# Output.net
KiCad netlist of a schematic drawn in EAGLE
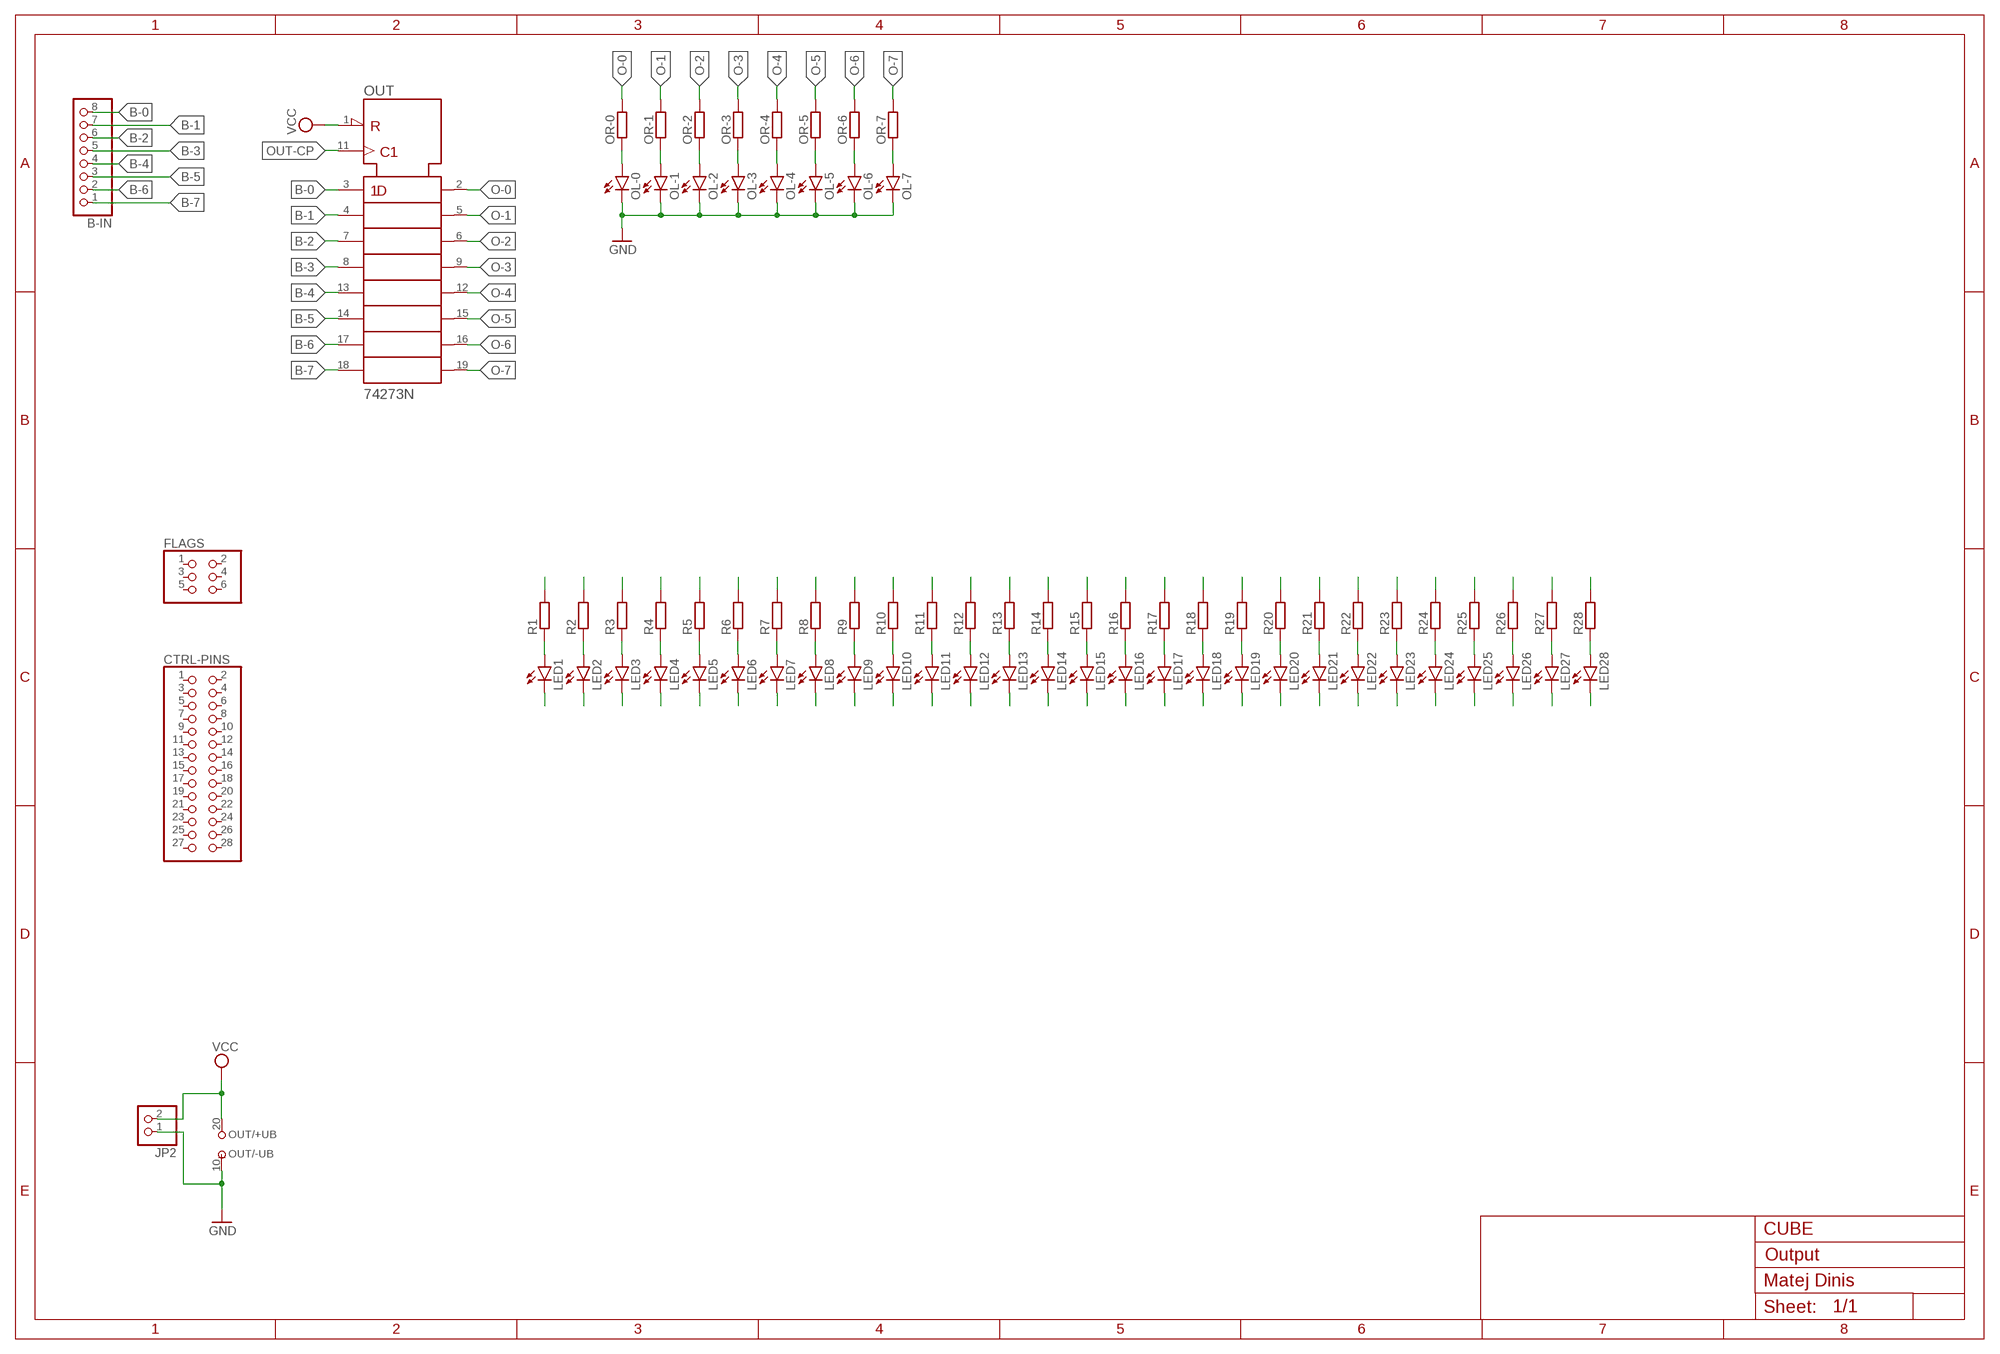
[diagram p0: schematic, sheet 1]

(export (version "E")
  (design (tool "Eeschema 10.0.6"))
  (components
    (comp (ref "B-IN")
      (value "PINHD-1X8")
      (footprint "eagle-import:1X08")
      (libsource (lib "eagle-import") (part "PINHD-1X8"))
    )
    (comp (ref "CTRL-PINS")
      (value "PINHD-2X14")
      (footprint "eagle-import:2X14")
      (libsource (lib "eagle-import") (part "PINHD-2X14"))
    )
    (comp (ref "FLAGS")
      (value "PINHD-2X3")
      (footprint "eagle-import:2X03")
      (libsource (lib "eagle-import") (part "PINHD-2X3"))
    )
    (comp (ref "JP2")
      (value "PINHD-1X2")
      (footprint "eagle-import:1X02")
      (libsource (lib "eagle-import") (part "PINHD-1X2"))
    )
    (comp (ref "LED1")
      (value "LED5MM")
      (footprint "eagle-import:LED5MM")
      (libsource (lib "eagle-import") (part "LED5MM"))
    )
    (comp (ref "LED2")
      (value "LED5MM")
      (footprint "eagle-import:LED5MM")
      (libsource (lib "eagle-import") (part "LED5MM"))
    )
    (comp (ref "LED3")
      (value "LED5MM")
      (footprint "eagle-import:LED5MM")
      (libsource (lib "eagle-import") (part "LED5MM"))
    )
    (comp (ref "LED4")
      (value "LED5MM")
      (footprint "eagle-import:LED5MM")
      (libsource (lib "eagle-import") (part "LED5MM"))
    )
    (comp (ref "LED5")
      (value "LED5MM")
      (footprint "eagle-import:LED5MM")
      (libsource (lib "eagle-import") (part "LED5MM"))
    )
    (comp (ref "LED6")
      (value "LED5MM")
      (footprint "eagle-import:LED5MM")
      (libsource (lib "eagle-import") (part "LED5MM"))
    )
    (comp (ref "LED7")
      (value "LED5MM")
      (footprint "eagle-import:LED5MM")
      (libsource (lib "eagle-import") (part "LED5MM"))
    )
    (comp (ref "LED8")
      (value "LED5MM")
      (footprint "eagle-import:LED5MM")
      (libsource (lib "eagle-import") (part "LED5MM"))
    )
    (comp (ref "LED9")
      (value "LED5MM")
      (footprint "eagle-import:LED5MM")
      (libsource (lib "eagle-import") (part "LED5MM"))
    )
    (comp (ref "LED10")
      (value "LED5MM")
      (footprint "eagle-import:LED5MM")
      (libsource (lib "eagle-import") (part "LED5MM"))
    )
    (comp (ref "LED11")
      (value "LED5MM")
      (footprint "eagle-import:LED5MM")
      (libsource (lib "eagle-import") (part "LED5MM"))
    )
    (comp (ref "LED12")
      (value "LED5MM")
      (footprint "eagle-import:LED5MM")
      (libsource (lib "eagle-import") (part "LED5MM"))
    )
    (comp (ref "LED13")
      (value "LED5MM")
      (footprint "eagle-import:LED5MM")
      (libsource (lib "eagle-import") (part "LED5MM"))
    )
    (comp (ref "LED14")
      (value "LED5MM")
      (footprint "eagle-import:LED5MM")
      (libsource (lib "eagle-import") (part "LED5MM"))
    )
    (comp (ref "LED15")
      (value "LED5MM")
      (footprint "eagle-import:LED5MM")
      (libsource (lib "eagle-import") (part "LED5MM"))
    )
    (comp (ref "LED16")
      (value "LED5MM")
      (footprint "eagle-import:LED5MM")
      (libsource (lib "eagle-import") (part "LED5MM"))
    )
    (comp (ref "LED17")
      (value "LED5MM")
      (footprint "eagle-import:LED5MM")
      (libsource (lib "eagle-import") (part "LED5MM"))
    )
    (comp (ref "LED18")
      (value "LED5MM")
      (footprint "eagle-import:LED5MM")
      (libsource (lib "eagle-import") (part "LED5MM"))
    )
    (comp (ref "LED19")
      (value "LED5MM")
      (footprint "eagle-import:LED5MM")
      (libsource (lib "eagle-import") (part "LED5MM"))
    )
    (comp (ref "LED20")
      (value "LED5MM")
      (footprint "eagle-import:LED5MM")
      (libsource (lib "eagle-import") (part "LED5MM"))
    )
    (comp (ref "LED21")
      (value "LED5MM")
      (footprint "eagle-import:LED5MM")
      (libsource (lib "eagle-import") (part "LED5MM"))
    )
    (comp (ref "LED22")
      (value "LED5MM")
      (footprint "eagle-import:LED5MM")
      (libsource (lib "eagle-import") (part "LED5MM"))
    )
    (comp (ref "LED23")
      (value "LED5MM")
      (footprint "eagle-import:LED5MM")
      (libsource (lib "eagle-import") (part "LED5MM"))
    )
    (comp (ref "LED24")
      (value "LED5MM")
      (footprint "eagle-import:LED5MM")
      (libsource (lib "eagle-import") (part "LED5MM"))
    )
    (comp (ref "LED25")
      (value "LED5MM")
      (footprint "eagle-import:LED5MM")
      (libsource (lib "eagle-import") (part "LED5MM"))
    )
    (comp (ref "LED26")
      (value "LED5MM")
      (footprint "eagle-import:LED5MM")
      (libsource (lib "eagle-import") (part "LED5MM"))
    )
    (comp (ref "LED27")
      (value "LED5MM")
      (footprint "eagle-import:LED5MM")
      (libsource (lib "eagle-import") (part "LED5MM"))
    )
    (comp (ref "LED28")
      (value "LED5MM")
      (footprint "eagle-import:LED5MM")
      (libsource (lib "eagle-import") (part "LED5MM"))
    )
    (comp (ref "OL-0")
      (value "LED5MM")
      (footprint "eagle-import:LED5MM")
      (libsource (lib "eagle-import") (part "LED5MM"))
    )
    (comp (ref "OL-1")
      (value "LED5MM")
      (footprint "eagle-import:LED5MM")
      (libsource (lib "eagle-import") (part "LED5MM"))
    )
    (comp (ref "OL-2")
      (value "LED5MM")
      (footprint "eagle-import:LED5MM")
      (libsource (lib "eagle-import") (part "LED5MM"))
    )
    (comp (ref "OL-3")
      (value "LED5MM")
      (footprint "eagle-import:LED5MM")
      (libsource (lib "eagle-import") (part "LED5MM"))
    )
    (comp (ref "OL-4")
      (value "LED5MM")
      (footprint "eagle-import:LED5MM")
      (libsource (lib "eagle-import") (part "LED5MM"))
    )
    (comp (ref "OL-5")
      (value "LED5MM")
      (footprint "eagle-import:LED5MM")
      (libsource (lib "eagle-import") (part "LED5MM"))
    )
    (comp (ref "OL-6")
      (value "LED5MM")
      (footprint "eagle-import:LED5MM")
      (libsource (lib "eagle-import") (part "LED5MM"))
    )
    (comp (ref "OL-7")
      (value "LED5MM")
      (footprint "eagle-import:LED5MM")
      (libsource (lib "eagle-import") (part "LED5MM"))
    )
    (comp (ref "OR-0")
      (value "R-EU_0207/10")
      (footprint "eagle-import:0207_10")
      (libsource (lib "eagle-import") (part "R-EU_0207/10"))
    )
    (comp (ref "OR-1")
      (value "R-EU_0207/10")
      (footprint "eagle-import:0207_10")
      (libsource (lib "eagle-import") (part "R-EU_0207/10"))
    )
    (comp (ref "OR-2")
      (value "R-EU_0207/10")
      (footprint "eagle-import:0207_10")
      (libsource (lib "eagle-import") (part "R-EU_0207/10"))
    )
    (comp (ref "OR-3")
      (value "R-EU_0207/10")
      (footprint "eagle-import:0207_10")
      (libsource (lib "eagle-import") (part "R-EU_0207/10"))
    )
    (comp (ref "OR-4")
      (value "R-EU_0207/10")
      (footprint "eagle-import:0207_10")
      (libsource (lib "eagle-import") (part "R-EU_0207/10"))
    )
    (comp (ref "OR-5")
      (value "R-EU_0207/10")
      (footprint "eagle-import:0207_10")
      (libsource (lib "eagle-import") (part "R-EU_0207/10"))
    )
    (comp (ref "OR-6")
      (value "R-EU_0207/10")
      (footprint "eagle-import:0207_10")
      (libsource (lib "eagle-import") (part "R-EU_0207/10"))
    )
    (comp (ref "OR-7")
      (value "R-EU_0207/10")
      (footprint "eagle-import:0207_10")
      (libsource (lib "eagle-import") (part "R-EU_0207/10"))
    )
    (comp (ref "OUT")
      (value "74273N")
      (footprint "eagle-import:DIL20")
      (libsource (lib "eagle-import") (part "74273N"))
    )
    (comp (ref "R1")
      (value "R-EU_0207/10")
      (footprint "eagle-import:0207_10")
      (libsource (lib "eagle-import") (part "R-EU_0207/10"))
    )
    (comp (ref "R2")
      (value "R-EU_0207/10")
      (footprint "eagle-import:0207_10")
      (libsource (lib "eagle-import") (part "R-EU_0207/10"))
    )
    (comp (ref "R3")
      (value "R-EU_0207/10")
      (footprint "eagle-import:0207_10")
      (libsource (lib "eagle-import") (part "R-EU_0207/10"))
    )
    (comp (ref "R4")
      (value "R-EU_0207/10")
      (footprint "eagle-import:0207_10")
      (libsource (lib "eagle-import") (part "R-EU_0207/10"))
    )
    (comp (ref "R5")
      (value "R-EU_0207/10")
      (footprint "eagle-import:0207_10")
      (libsource (lib "eagle-import") (part "R-EU_0207/10"))
    )
    (comp (ref "R6")
      (value "R-EU_0207/10")
      (footprint "eagle-import:0207_10")
      (libsource (lib "eagle-import") (part "R-EU_0207/10"))
    )
    (comp (ref "R7")
      (value "R-EU_0207/10")
      (footprint "eagle-import:0207_10")
      (libsource (lib "eagle-import") (part "R-EU_0207/10"))
    )
    (comp (ref "R8")
      (value "R-EU_0207/10")
      (footprint "eagle-import:0207_10")
      (libsource (lib "eagle-import") (part "R-EU_0207/10"))
    )
    (comp (ref "R9")
      (value "R-EU_0207/10")
      (footprint "eagle-import:0207_10")
      (libsource (lib "eagle-import") (part "R-EU_0207/10"))
    )
    (comp (ref "R10")
      (value "R-EU_0207/10")
      (footprint "eagle-import:0207_10")
      (libsource (lib "eagle-import") (part "R-EU_0207/10"))
    )
    (comp (ref "R11")
      (value "R-EU_0207/10")
      (footprint "eagle-import:0207_10")
      (libsource (lib "eagle-import") (part "R-EU_0207/10"))
    )
    (comp (ref "R12")
      (value "R-EU_0207/10")
      (footprint "eagle-import:0207_10")
      (libsource (lib "eagle-import") (part "R-EU_0207/10"))
    )
    (comp (ref "R13")
      (value "R-EU_0207/10")
      (footprint "eagle-import:0207_10")
      (libsource (lib "eagle-import") (part "R-EU_0207/10"))
    )
    (comp (ref "R14")
      (value "R-EU_0207/10")
      (footprint "eagle-import:0207_10")
      (libsource (lib "eagle-import") (part "R-EU_0207/10"))
    )
    (comp (ref "R15")
      (value "R-EU_0207/10")
      (footprint "eagle-import:0207_10")
      (libsource (lib "eagle-import") (part "R-EU_0207/10"))
    )
    (comp (ref "R16")
      (value "R-EU_0207/10")
      (footprint "eagle-import:0207_10")
      (libsource (lib "eagle-import") (part "R-EU_0207/10"))
    )
    (comp (ref "R17")
      (value "R-EU_0207/10")
      (footprint "eagle-import:0207_10")
      (libsource (lib "eagle-import") (part "R-EU_0207/10"))
    )
    (comp (ref "R18")
      (value "R-EU_0207/10")
      (footprint "eagle-import:0207_10")
      (libsource (lib "eagle-import") (part "R-EU_0207/10"))
    )
    (comp (ref "R19")
      (value "R-EU_0207/10")
      (footprint "eagle-import:0207_10")
      (libsource (lib "eagle-import") (part "R-EU_0207/10"))
    )
    (comp (ref "R20")
      (value "R-EU_0207/10")
      (footprint "eagle-import:0207_10")
      (libsource (lib "eagle-import") (part "R-EU_0207/10"))
    )
    (comp (ref "R21")
      (value "R-EU_0207/10")
      (footprint "eagle-import:0207_10")
      (libsource (lib "eagle-import") (part "R-EU_0207/10"))
    )
    (comp (ref "R22")
      (value "R-EU_0207/10")
      (footprint "eagle-import:0207_10")
      (libsource (lib "eagle-import") (part "R-EU_0207/10"))
    )
    (comp (ref "R23")
      (value "R-EU_0207/10")
      (footprint "eagle-import:0207_10")
      (libsource (lib "eagle-import") (part "R-EU_0207/10"))
    )
    (comp (ref "R24")
      (value "R-EU_0207/10")
      (footprint "eagle-import:0207_10")
      (libsource (lib "eagle-import") (part "R-EU_0207/10"))
    )
    (comp (ref "R25")
      (value "R-EU_0207/10")
      (footprint "eagle-import:0207_10")
      (libsource (lib "eagle-import") (part "R-EU_0207/10"))
    )
    (comp (ref "R26")
      (value "R-EU_0207/10")
      (footprint "eagle-import:0207_10")
      (libsource (lib "eagle-import") (part "R-EU_0207/10"))
    )
    (comp (ref "R27")
      (value "R-EU_0207/10")
      (footprint "eagle-import:0207_10")
      (libsource (lib "eagle-import") (part "R-EU_0207/10"))
    )
    (comp (ref "R28")
      (value "R-EU_0207/10")
      (footprint "eagle-import:0207_10")
      (libsource (lib "eagle-import") (part "R-EU_0207/10"))
    )
  )
  (nets
    (net (code "1") (name "B-0") (class "Default")
      (node (ref "B-IN") (pin "8") (pinfunction "8_8") (pintype "passive"))
      (node (ref "OUT") (pin "3") (pinfunction "1D_3") (pintype "input"))
    )
    (net (code "2") (name "B-1") (class "Default")
      (node (ref "B-IN") (pin "7") (pinfunction "7_7") (pintype "passive"))
      (node (ref "OUT") (pin "4") (pinfunction "2D_4") (pintype "input"))
    )
    (net (code "3") (name "B-2") (class "Default")
      (node (ref "B-IN") (pin "6") (pinfunction "6_6") (pintype "passive"))
      (node (ref "OUT") (pin "7") (pinfunction "3D_7") (pintype "input"))
    )
    (net (code "4") (name "B-3") (class "Default")
      (node (ref "B-IN") (pin "5") (pinfunction "5_5") (pintype "passive"))
      (node (ref "OUT") (pin "8") (pinfunction "4D_8") (pintype "input"))
    )
    (net (code "5") (name "B-4") (class "Default")
      (node (ref "B-IN") (pin "4") (pinfunction "4_4") (pintype "passive"))
      (node (ref "OUT") (pin "13") (pinfunction "5D_13") (pintype "input"))
    )
    (net (code "6") (name "B-5") (class "Default")
      (node (ref "B-IN") (pin "3") (pinfunction "3_3") (pintype "passive"))
      (node (ref "OUT") (pin "14") (pinfunction "6D_14") (pintype "input"))
    )
    (net (code "7") (name "B-6") (class "Default")
      (node (ref "B-IN") (pin "2") (pinfunction "2_2") (pintype "passive"))
      (node (ref "OUT") (pin "17") (pinfunction "7D_17") (pintype "input"))
    )
    (net (code "8") (name "B-7") (class "Default")
      (node (ref "B-IN") (pin "1") (pinfunction "1_1") (pintype "passive"))
      (node (ref "OUT") (pin "18") (pinfunction "8D_18") (pintype "input"))
    )
    (net (code "9") (name "GND") (class "Default")
      (node (ref "JP2") (pin "1") (pinfunction "1_1") (pintype "passive"))
      (node (ref "OL-0") (pin "K") (pinfunction "C_K") (pintype "passive"))
      (node (ref "OL-1") (pin "K") (pinfunction "C_K") (pintype "passive"))
      (node (ref "OL-2") (pin "K") (pinfunction "C_K") (pintype "passive"))
      (node (ref "OL-3") (pin "K") (pinfunction "C_K") (pintype "passive"))
      (node (ref "OL-4") (pin "K") (pinfunction "C_K") (pintype "passive"))
      (node (ref "OL-5") (pin "K") (pinfunction "C_K") (pintype "passive"))
      (node (ref "OL-6") (pin "K") (pinfunction "C_K") (pintype "passive"))
      (node (ref "OL-7") (pin "K") (pinfunction "C_K") (pintype "passive"))
      (node (ref "OUT") (pin "10") (pinfunction "-UB_10") (pintype "power_in"))
    )
    (net (code "10") (name "Net-(LED1-PadA)") (class "Default")
      (node (ref "LED1") (pin "A") (pinfunction "A_A") (pintype "passive"))
      (node (ref "R1") (pin "1") (pinfunction "1_1") (pintype "passive"))
    )
    (net (code "11") (name "Net-(LED2-PadA)") (class "Default")
      (node (ref "LED2") (pin "A") (pinfunction "A_A") (pintype "passive"))
      (node (ref "R2") (pin "1") (pinfunction "1_1") (pintype "passive"))
    )
    (net (code "12") (name "Net-(LED3-PadA)") (class "Default")
      (node (ref "LED3") (pin "A") (pinfunction "A_A") (pintype "passive"))
      (node (ref "R3") (pin "1") (pinfunction "1_1") (pintype "passive"))
    )
    (net (code "13") (name "Net-(LED4-PadA)") (class "Default")
      (node (ref "LED4") (pin "A") (pinfunction "A_A") (pintype "passive"))
      (node (ref "R4") (pin "1") (pinfunction "1_1") (pintype "passive"))
    )
    (net (code "14") (name "Net-(LED5-PadA)") (class "Default")
      (node (ref "LED5") (pin "A") (pinfunction "A_A") (pintype "passive"))
      (node (ref "R5") (pin "1") (pinfunction "1_1") (pintype "passive"))
    )
    (net (code "15") (name "Net-(LED6-PadA)") (class "Default")
      (node (ref "LED6") (pin "A") (pinfunction "A_A") (pintype "passive"))
      (node (ref "R6") (pin "1") (pinfunction "1_1") (pintype "passive"))
    )
    (net (code "16") (name "Net-(LED7-PadA)") (class "Default")
      (node (ref "LED7") (pin "A") (pinfunction "A_A") (pintype "passive"))
      (node (ref "R7") (pin "1") (pinfunction "1_1") (pintype "passive"))
    )
    (net (code "17") (name "Net-(LED8-PadA)") (class "Default")
      (node (ref "LED8") (pin "A") (pinfunction "A_A") (pintype "passive"))
      (node (ref "R8") (pin "1") (pinfunction "1_1") (pintype "passive"))
    )
    (net (code "18") (name "Net-(LED9-PadA)") (class "Default")
      (node (ref "LED9") (pin "A") (pinfunction "A_A") (pintype "passive"))
      (node (ref "R9") (pin "1") (pinfunction "1_1") (pintype "passive"))
    )
    (net (code "19") (name "Net-(LED10-PadA)") (class "Default")
      (node (ref "LED10") (pin "A") (pinfunction "A_A") (pintype "passive"))
      (node (ref "R10") (pin "1") (pinfunction "1_1") (pintype "passive"))
    )
    (net (code "20") (name "Net-(LED11-PadA)") (class "Default")
      (node (ref "LED11") (pin "A") (pinfunction "A_A") (pintype "passive"))
      (node (ref "R11") (pin "1") (pinfunction "1_1") (pintype "passive"))
    )
    (net (code "21") (name "Net-(LED12-PadA)") (class "Default")
      (node (ref "LED12") (pin "A") (pinfunction "A_A") (pintype "passive"))
      (node (ref "R12") (pin "1") (pinfunction "1_1") (pintype "passive"))
    )
    (net (code "22") (name "Net-(LED13-PadA)") (class "Default")
      (node (ref "LED13") (pin "A") (pinfunction "A_A") (pintype "passive"))
      (node (ref "R13") (pin "1") (pinfunction "1_1") (pintype "passive"))
    )
    (net (code "23") (name "Net-(LED14-PadA)") (class "Default")
      (node (ref "LED14") (pin "A") (pinfunction "A_A") (pintype "passive"))
      (node (ref "R14") (pin "1") (pinfunction "1_1") (pintype "passive"))
    )
    (net (code "24") (name "Net-(LED15-PadA)") (class "Default")
      (node (ref "LED15") (pin "A") (pinfunction "A_A") (pintype "passive"))
      (node (ref "R15") (pin "1") (pinfunction "1_1") (pintype "passive"))
    )
    (net (code "25") (name "Net-(LED16-PadA)") (class "Default")
      (node (ref "LED16") (pin "A") (pinfunction "A_A") (pintype "passive"))
      (node (ref "R16") (pin "1") (pinfunction "1_1") (pintype "passive"))
    )
    (net (code "26") (name "Net-(LED17-PadA)") (class "Default")
      (node (ref "LED17") (pin "A") (pinfunction "A_A") (pintype "passive"))
      (node (ref "R17") (pin "1") (pinfunction "1_1") (pintype "passive"))
    )
    (net (code "27") (name "Net-(LED18-PadA)") (class "Default")
      (node (ref "LED18") (pin "A") (pinfunction "A_A") (pintype "passive"))
      (node (ref "R18") (pin "1") (pinfunction "1_1") (pintype "passive"))
    )
    (net (code "28") (name "Net-(LED19-PadA)") (class "Default")
      (node (ref "LED19") (pin "A") (pinfunction "A_A") (pintype "passive"))
      (node (ref "R19") (pin "1") (pinfunction "1_1") (pintype "passive"))
    )
    (net (code "29") (name "Net-(LED20-PadA)") (class "Default")
      (node (ref "LED20") (pin "A") (pinfunction "A_A") (pintype "passive"))
      (node (ref "R20") (pin "1") (pinfunction "1_1") (pintype "passive"))
    )
    (net (code "30") (name "Net-(LED21-PadA)") (class "Default")
      (node (ref "LED21") (pin "A") (pinfunction "A_A") (pintype "passive"))
      (node (ref "R21") (pin "1") (pinfunction "1_1") (pintype "passive"))
    )
    (net (code "31") (name "Net-(LED22-PadA)") (class "Default")
      (node (ref "LED22") (pin "A") (pinfunction "A_A") (pintype "passive"))
      (node (ref "R22") (pin "1") (pinfunction "1_1") (pintype "passive"))
    )
    (net (code "32") (name "Net-(LED23-PadA)") (class "Default")
      (node (ref "LED23") (pin "A") (pinfunction "A_A") (pintype "passive"))
      (node (ref "R23") (pin "1") (pinfunction "1_1") (pintype "passive"))
    )
    (net (code "33") (name "Net-(LED24-PadA)") (class "Default")
      (node (ref "LED24") (pin "A") (pinfunction "A_A") (pintype "passive"))
      (node (ref "R24") (pin "1") (pinfunction "1_1") (pintype "passive"))
    )
    (net (code "34") (name "Net-(LED25-PadA)") (class "Default")
      (node (ref "LED25") (pin "A") (pinfunction "A_A") (pintype "passive"))
      (node (ref "R25") (pin "1") (pinfunction "1_1") (pintype "passive"))
    )
    (net (code "35") (name "Net-(LED26-PadA)") (class "Default")
      (node (ref "LED26") (pin "A") (pinfunction "A_A") (pintype "passive"))
      (node (ref "R26") (pin "1") (pinfunction "1_1") (pintype "passive"))
    )
    (net (code "36") (name "Net-(LED27-PadA)") (class "Default")
      (node (ref "LED27") (pin "A") (pinfunction "A_A") (pintype "passive"))
      (node (ref "R27") (pin "1") (pinfunction "1_1") (pintype "passive"))
    )
    (net (code "37") (name "Net-(LED28-PadA)") (class "Default")
      (node (ref "LED28") (pin "A") (pinfunction "A_A") (pintype "passive"))
      (node (ref "R28") (pin "1") (pinfunction "1_1") (pintype "passive"))
    )
    (net (code "38") (name "Net-(OL-0-PadA)") (class "Default")
      (node (ref "OL-0") (pin "A") (pinfunction "A_A") (pintype "passive"))
      (node (ref "OR-0") (pin "1") (pinfunction "1_1") (pintype "passive"))
    )
    (net (code "39") (name "Net-(OL-1-PadA)") (class "Default")
      (node (ref "OL-1") (pin "A") (pinfunction "A_A") (pintype "passive"))
      (node (ref "OR-1") (pin "1") (pinfunction "1_1") (pintype "passive"))
    )
    (net (code "40") (name "Net-(OL-2-PadA)") (class "Default")
      (node (ref "OL-2") (pin "A") (pinfunction "A_A") (pintype "passive"))
      (node (ref "OR-2") (pin "1") (pinfunction "1_1") (pintype "passive"))
    )
    (net (code "41") (name "Net-(OL-3-PadA)") (class "Default")
      (node (ref "OL-3") (pin "A") (pinfunction "A_A") (pintype "passive"))
      (node (ref "OR-3") (pin "1") (pinfunction "1_1") (pintype "passive"))
    )
    (net (code "42") (name "Net-(OL-4-PadA)") (class "Default")
      (node (ref "OL-4") (pin "A") (pinfunction "A_A") (pintype "passive"))
      (node (ref "OR-4") (pin "1") (pinfunction "1_1") (pintype "passive"))
    )
    (net (code "43") (name "Net-(OL-5-PadA)") (class "Default")
      (node (ref "OL-5") (pin "A") (pinfunction "A_A") (pintype "passive"))
      (node (ref "OR-5") (pin "1") (pinfunction "1_1") (pintype "passive"))
    )
    (net (code "44") (name "Net-(OL-6-PadA)") (class "Default")
      (node (ref "OL-6") (pin "A") (pinfunction "A_A") (pintype "passive"))
      (node (ref "OR-6") (pin "1") (pinfunction "1_1") (pintype "passive"))
    )
    (net (code "45") (name "Net-(OL-7-PadA)") (class "Default")
      (node (ref "OL-7") (pin "A") (pinfunction "A_A") (pintype "passive"))
      (node (ref "OR-7") (pin "1") (pinfunction "1_1") (pintype "passive"))
    )
    (net (code "46") (name "O-0") (class "Default")
      (node (ref "OR-0") (pin "2") (pinfunction "2_2") (pintype "passive"))
      (node (ref "OUT") (pin "2") (pinfunction "1Q_2") (pintype "output"))
    )
    (net (code "47") (name "O-1") (class "Default")
      (node (ref "OR-1") (pin "2") (pinfunction "2_2") (pintype "passive"))
      (node (ref "OUT") (pin "5") (pinfunction "2Q_5") (pintype "output"))
    )
    (net (code "48") (name "O-2") (class "Default")
      (node (ref "OR-2") (pin "2") (pinfunction "2_2") (pintype "passive"))
      (node (ref "OUT") (pin "6") (pinfunction "3Q_6") (pintype "output"))
    )
    (net (code "49") (name "O-3") (class "Default")
      (node (ref "OR-3") (pin "2") (pinfunction "2_2") (pintype "passive"))
      (node (ref "OUT") (pin "9") (pinfunction "4Q_9") (pintype "output"))
    )
    (net (code "50") (name "O-4") (class "Default")
      (node (ref "OR-4") (pin "2") (pinfunction "2_2") (pintype "passive"))
      (node (ref "OUT") (pin "12") (pinfunction "5Q_12") (pintype "output"))
    )
    (net (code "51") (name "O-5") (class "Default")
      (node (ref "OR-5") (pin "2") (pinfunction "2_2") (pintype "passive"))
      (node (ref "OUT") (pin "15") (pinfunction "6Q_15") (pintype "output"))
    )
    (net (code "52") (name "O-6") (class "Default")
      (node (ref "OR-6") (pin "2") (pinfunction "2_2") (pintype "passive"))
      (node (ref "OUT") (pin "16") (pinfunction "7Q_16") (pintype "output"))
    )
    (net (code "53") (name "O-7") (class "Default")
      (node (ref "OR-7") (pin "2") (pinfunction "2_2") (pintype "passive"))
      (node (ref "OUT") (pin "19") (pinfunction "8Q_19") (pintype "output"))
    )
    (net (code "54") (name "OUT-CP") (class "Default")
      (node (ref "OUT") (pin "11") (pinfunction "CLK_11") (pintype "input"))
    )
    (net (code "55") (name "VCC") (class "Default")
      (node (ref "JP2") (pin "2") (pinfunction "2_2") (pintype "passive"))
      (node (ref "OUT") (pin "1") (pinfunction "~{CLR}_1") (pintype "input"))
      (node (ref "OUT") (pin "20") (pinfunction "+UB_20") (pintype "power_in"))
    )
    (net (code "56") (name "unconnected-(CTRL-PINS-Pad1)") (class "Default")
      (node (ref "CTRL-PINS") (pin "1") (pinfunction "1_1") (pintype "passive"))
    )
    (net (code "57") (name "unconnected-(CTRL-PINS-Pad2)") (class "Default")
      (node (ref "CTRL-PINS") (pin "2") (pinfunction "2_2") (pintype "passive"))
    )
    (net (code "58") (name "unconnected-(CTRL-PINS-Pad3)") (class "Default")
      (node (ref "CTRL-PINS") (pin "3") (pinfunction "3_3") (pintype "passive"))
    )
    (net (code "59") (name "unconnected-(CTRL-PINS-Pad4)") (class "Default")
      (node (ref "CTRL-PINS") (pin "4") (pinfunction "4_4") (pintype "passive"))
    )
    (net (code "60") (name "unconnected-(CTRL-PINS-Pad5)") (class "Default")
      (node (ref "CTRL-PINS") (pin "5") (pinfunction "5_5") (pintype "passive"))
    )
    (net (code "61") (name "unconnected-(CTRL-PINS-Pad6)") (class "Default")
      (node (ref "CTRL-PINS") (pin "6") (pinfunction "6_6") (pintype "passive"))
    )
    (net (code "62") (name "unconnected-(CTRL-PINS-Pad7)") (class "Default")
      (node (ref "CTRL-PINS") (pin "7") (pinfunction "7_7") (pintype "passive"))
    )
    (net (code "63") (name "unconnected-(CTRL-PINS-Pad8)") (class "Default")
      (node (ref "CTRL-PINS") (pin "8") (pinfunction "8_8") (pintype "passive"))
    )
    (net (code "64") (name "unconnected-(CTRL-PINS-Pad9)") (class "Default")
      (node (ref "CTRL-PINS") (pin "9") (pinfunction "9_9") (pintype "passive"))
    )
    (net (code "65") (name "unconnected-(CTRL-PINS-Pad10)") (class "Default")
      (node (ref "CTRL-PINS") (pin "10") (pinfunction "10_10") (pintype "passive"))
    )
    (net (code "66") (name "unconnected-(CTRL-PINS-Pad11)") (class "Default")
      (node (ref "CTRL-PINS") (pin "11") (pinfunction "11_11") (pintype "passive"))
    )
    (net (code "67") (name "unconnected-(CTRL-PINS-Pad12)") (class "Default")
      (node (ref "CTRL-PINS") (pin "12") (pinfunction "12_12") (pintype "passive"))
    )
    (net (code "68") (name "unconnected-(CTRL-PINS-Pad13)") (class "Default")
      (node (ref "CTRL-PINS") (pin "13") (pinfunction "13_13") (pintype "passive"))
    )
    (net (code "69") (name "unconnected-(CTRL-PINS-Pad14)") (class "Default")
      (node (ref "CTRL-PINS") (pin "14") (pinfunction "14_14") (pintype "passive"))
    )
    (net (code "70") (name "unconnected-(CTRL-PINS-Pad15)") (class "Default")
      (node (ref "CTRL-PINS") (pin "15") (pinfunction "15_15") (pintype "passive"))
    )
    (net (code "71") (name "unconnected-(CTRL-PINS-Pad16)") (class "Default")
      (node (ref "CTRL-PINS") (pin "16") (pinfunction "16_16") (pintype "passive"))
    )
    (net (code "72") (name "unconnected-(CTRL-PINS-Pad17)") (class "Default")
      (node (ref "CTRL-PINS") (pin "17") (pinfunction "17_17") (pintype "passive"))
    )
    (net (code "73") (name "unconnected-(CTRL-PINS-Pad18)") (class "Default")
      (node (ref "CTRL-PINS") (pin "18") (pinfunction "18_18") (pintype "passive"))
    )
    (net (code "74") (name "unconnected-(CTRL-PINS-Pad19)") (class "Default")
      (node (ref "CTRL-PINS") (pin "19") (pinfunction "19_19") (pintype "passive"))
    )
    (net (code "75") (name "unconnected-(CTRL-PINS-Pad20)") (class "Default")
      (node (ref "CTRL-PINS") (pin "20") (pinfunction "20_20") (pintype "passive"))
    )
    (net (code "76") (name "unconnected-(CTRL-PINS-Pad21)") (class "Default")
      (node (ref "CTRL-PINS") (pin "21") (pinfunction "21_21") (pintype "passive"))
    )
    (net (code "77") (name "unconnected-(CTRL-PINS-Pad22)") (class "Default")
      (node (ref "CTRL-PINS") (pin "22") (pinfunction "22_22") (pintype "passive"))
    )
    (net (code "78") (name "unconnected-(CTRL-PINS-Pad23)") (class "Default")
      (node (ref "CTRL-PINS") (pin "23") (pinfunction "23_23") (pintype "passive"))
    )
    (net (code "79") (name "unconnected-(CTRL-PINS-Pad24)") (class "Default")
      (node (ref "CTRL-PINS") (pin "24") (pinfunction "24_24") (pintype "passive"))
    )
    (net (code "80") (name "unconnected-(CTRL-PINS-Pad25)") (class "Default")
      (node (ref "CTRL-PINS") (pin "25") (pinfunction "25_25") (pintype "passive"))
    )
    (net (code "81") (name "unconnected-(CTRL-PINS-Pad26)") (class "Default")
      (node (ref "CTRL-PINS") (pin "26") (pinfunction "26_26") (pintype "passive"))
    )
    (net (code "82") (name "unconnected-(CTRL-PINS-Pad27)") (class "Default")
      (node (ref "CTRL-PINS") (pin "27") (pinfunction "27_27") (pintype "passive"))
    )
    (net (code "83") (name "unconnected-(CTRL-PINS-Pad28)") (class "Default")
      (node (ref "CTRL-PINS") (pin "28") (pinfunction "28_28") (pintype "passive"))
    )
    (net (code "84") (name "unconnected-(FLAGS-Pad1)") (class "Default")
      (node (ref "FLAGS") (pin "1") (pinfunction "1_1") (pintype "passive"))
    )
    (net (code "85") (name "unconnected-(FLAGS-Pad2)") (class "Default")
      (node (ref "FLAGS") (pin "2") (pinfunction "2_2") (pintype "passive"))
    )
    (net (code "86") (name "unconnected-(FLAGS-Pad3)") (class "Default")
      (node (ref "FLAGS") (pin "3") (pinfunction "3_3") (pintype "passive"))
    )
    (net (code "87") (name "unconnected-(FLAGS-Pad4)") (class "Default")
      (node (ref "FLAGS") (pin "4") (pinfunction "4_4") (pintype "passive"))
    )
    (net (code "88") (name "unconnected-(FLAGS-Pad5)") (class "Default")
      (node (ref "FLAGS") (pin "5") (pinfunction "5_5") (pintype "passive"))
    )
    (net (code "89") (name "unconnected-(FLAGS-Pad6)") (class "Default")
      (node (ref "FLAGS") (pin "6") (pinfunction "6_6") (pintype "passive"))
    )
    (net (code "90") (name "unconnected-(LED1-C-PadK)") (class "Default")
      (node (ref "LED1") (pin "K") (pinfunction "C_K") (pintype "passive"))
    )
    (net (code "91") (name "unconnected-(LED2-C-PadK)") (class "Default")
      (node (ref "LED2") (pin "K") (pinfunction "C_K") (pintype "passive"))
    )
    (net (code "92") (name "unconnected-(LED3-C-PadK)") (class "Default")
      (node (ref "LED3") (pin "K") (pinfunction "C_K") (pintype "passive"))
    )
    (net (code "93") (name "unconnected-(LED4-C-PadK)") (class "Default")
      (node (ref "LED4") (pin "K") (pinfunction "C_K") (pintype "passive"))
    )
    (net (code "94") (name "unconnected-(LED5-C-PadK)") (class "Default")
      (node (ref "LED5") (pin "K") (pinfunction "C_K") (pintype "passive"))
    )
    (net (code "95") (name "unconnected-(LED6-C-PadK)") (class "Default")
      (node (ref "LED6") (pin "K") (pinfunction "C_K") (pintype "passive"))
    )
    (net (code "96") (name "unconnected-(LED7-C-PadK)") (class "Default")
      (node (ref "LED7") (pin "K") (pinfunction "C_K") (pintype "passive"))
    )
    (net (code "97") (name "unconnected-(LED8-C-PadK)") (class "Default")
      (node (ref "LED8") (pin "K") (pinfunction "C_K") (pintype "passive"))
    )
    (net (code "98") (name "unconnected-(LED9-C-PadK)") (class "Default")
      (node (ref "LED9") (pin "K") (pinfunction "C_K") (pintype "passive"))
    )
    (net (code "99") (name "unconnected-(LED10-C-PadK)") (class "Default")
      (node (ref "LED10") (pin "K") (pinfunction "C_K") (pintype "passive"))
    )
    (net (code "100") (name "unconnected-(LED11-C-PadK)") (class "Default")
      (node (ref "LED11") (pin "K") (pinfunction "C_K") (pintype "passive"))
    )
    (net (code "101") (name "unconnected-(LED12-C-PadK)") (class "Default")
      (node (ref "LED12") (pin "K") (pinfunction "C_K") (pintype "passive"))
    )
    (net (code "102") (name "unconnected-(LED13-C-PadK)") (class "Default")
      (node (ref "LED13") (pin "K") (pinfunction "C_K") (pintype "passive"))
    )
    (net (code "103") (name "unconnected-(LED14-C-PadK)") (class "Default")
      (node (ref "LED14") (pin "K") (pinfunction "C_K") (pintype "passive"))
    )
    (net (code "104") (name "unconnected-(LED15-C-PadK)") (class "Default")
      (node (ref "LED15") (pin "K") (pinfunction "C_K") (pintype "passive"))
    )
    (net (code "105") (name "unconnected-(LED16-C-PadK)") (class "Default")
      (node (ref "LED16") (pin "K") (pinfunction "C_K") (pintype "passive"))
    )
    (net (code "106") (name "unconnected-(LED17-C-PadK)") (class "Default")
      (node (ref "LED17") (pin "K") (pinfunction "C_K") (pintype "passive"))
    )
    (net (code "107") (name "unconnected-(LED18-C-PadK)") (class "Default")
      (node (ref "LED18") (pin "K") (pinfunction "C_K") (pintype "passive"))
    )
    (net (code "108") (name "unconnected-(LED19-C-PadK)") (class "Default")
      (node (ref "LED19") (pin "K") (pinfunction "C_K") (pintype "passive"))
    )
    (net (code "109") (name "unconnected-(LED20-C-PadK)") (class "Default")
      (node (ref "LED20") (pin "K") (pinfunction "C_K") (pintype "passive"))
    )
    (net (code "110") (name "unconnected-(LED21-C-PadK)") (class "Default")
      (node (ref "LED21") (pin "K") (pinfunction "C_K") (pintype "passive"))
    )
    (net (code "111") (name "unconnected-(LED22-C-PadK)") (class "Default")
      (node (ref "LED22") (pin "K") (pinfunction "C_K") (pintype "passive"))
    )
    (net (code "112") (name "unconnected-(LED23-C-PadK)") (class "Default")
      (node (ref "LED23") (pin "K") (pinfunction "C_K") (pintype "passive"))
    )
    (net (code "113") (name "unconnected-(LED24-C-PadK)") (class "Default")
      (node (ref "LED24") (pin "K") (pinfunction "C_K") (pintype "passive"))
    )
    (net (code "114") (name "unconnected-(LED25-C-PadK)") (class "Default")
      (node (ref "LED25") (pin "K") (pinfunction "C_K") (pintype "passive"))
    )
    (net (code "115") (name "unconnected-(LED26-C-PadK)") (class "Default")
      (node (ref "LED26") (pin "K") (pinfunction "C_K") (pintype "passive"))
    )
    (net (code "116") (name "unconnected-(LED27-C-PadK)") (class "Default")
      (node (ref "LED27") (pin "K") (pinfunction "C_K") (pintype "passive"))
    )
    (net (code "117") (name "unconnected-(LED28-C-PadK)") (class "Default")
      (node (ref "LED28") (pin "K") (pinfunction "C_K") (pintype "passive"))
    )
    (net (code "118") (name "unconnected-(R1-Pad2)") (class "Default")
      (node (ref "R1") (pin "2") (pinfunction "2_2") (pintype "passive"))
    )
    (net (code "119") (name "unconnected-(R2-Pad2)") (class "Default")
      (node (ref "R2") (pin "2") (pinfunction "2_2") (pintype "passive"))
    )
    (net (code "120") (name "unconnected-(R3-Pad2)") (class "Default")
      (node (ref "R3") (pin "2") (pinfunction "2_2") (pintype "passive"))
    )
    (net (code "121") (name "unconnected-(R4-Pad2)") (class "Default")
      (node (ref "R4") (pin "2") (pinfunction "2_2") (pintype "passive"))
    )
    (net (code "122") (name "unconnected-(R5-Pad2)") (class "Default")
      (node (ref "R5") (pin "2") (pinfunction "2_2") (pintype "passive"))
    )
    (net (code "123") (name "unconnected-(R6-Pad2)") (class "Default")
      (node (ref "R6") (pin "2") (pinfunction "2_2") (pintype "passive"))
    )
    (net (code "124") (name "unconnected-(R7-Pad2)") (class "Default")
      (node (ref "R7") (pin "2") (pinfunction "2_2") (pintype "passive"))
    )
    (net (code "125") (name "unconnected-(R8-Pad2)") (class "Default")
      (node (ref "R8") (pin "2") (pinfunction "2_2") (pintype "passive"))
    )
    (net (code "126") (name "unconnected-(R9-Pad2)") (class "Default")
      (node (ref "R9") (pin "2") (pinfunction "2_2") (pintype "passive"))
    )
    (net (code "127") (name "unconnected-(R10-Pad2)") (class "Default")
      (node (ref "R10") (pin "2") (pinfunction "2_2") (pintype "passive"))
    )
    (net (code "128") (name "unconnected-(R11-Pad2)") (class "Default")
      (node (ref "R11") (pin "2") (pinfunction "2_2") (pintype "passive"))
    )
    (net (code "129") (name "unconnected-(R12-Pad2)") (class "Default")
      (node (ref "R12") (pin "2") (pinfunction "2_2") (pintype "passive"))
    )
    (net (code "130") (name "unconnected-(R13-Pad2)") (class "Default")
      (node (ref "R13") (pin "2") (pinfunction "2_2") (pintype "passive"))
    )
    (net (code "131") (name "unconnected-(R14-Pad2)") (class "Default")
      (node (ref "R14") (pin "2") (pinfunction "2_2") (pintype "passive"))
    )
    (net (code "132") (name "unconnected-(R15-Pad2)") (class "Default")
      (node (ref "R15") (pin "2") (pinfunction "2_2") (pintype "passive"))
    )
    (net (code "133") (name "unconnected-(R16-Pad2)") (class "Default")
      (node (ref "R16") (pin "2") (pinfunction "2_2") (pintype "passive"))
    )
    (net (code "134") (name "unconnected-(R17-Pad2)") (class "Default")
      (node (ref "R17") (pin "2") (pinfunction "2_2") (pintype "passive"))
    )
    (net (code "135") (name "unconnected-(R18-Pad2)") (class "Default")
      (node (ref "R18") (pin "2") (pinfunction "2_2") (pintype "passive"))
    )
    (net (code "136") (name "unconnected-(R19-Pad2)") (class "Default")
      (node (ref "R19") (pin "2") (pinfunction "2_2") (pintype "passive"))
    )
    (net (code "137") (name "unconnected-(R20-Pad2)") (class "Default")
      (node (ref "R20") (pin "2") (pinfunction "2_2") (pintype "passive"))
    )
    (net (code "138") (name "unconnected-(R21-Pad2)") (class "Default")
      (node (ref "R21") (pin "2") (pinfunction "2_2") (pintype "passive"))
    )
    (net (code "139") (name "unconnected-(R22-Pad2)") (class "Default")
      (node (ref "R22") (pin "2") (pinfunction "2_2") (pintype "passive"))
    )
    (net (code "140") (name "unconnected-(R23-Pad2)") (class "Default")
      (node (ref "R23") (pin "2") (pinfunction "2_2") (pintype "passive"))
    )
    (net (code "141") (name "unconnected-(R24-Pad2)") (class "Default")
      (node (ref "R24") (pin "2") (pinfunction "2_2") (pintype "passive"))
    )
    (net (code "142") (name "unconnected-(R25-Pad2)") (class "Default")
      (node (ref "R25") (pin "2") (pinfunction "2_2") (pintype "passive"))
    )
    (net (code "143") (name "unconnected-(R26-Pad2)") (class "Default")
      (node (ref "R26") (pin "2") (pinfunction "2_2") (pintype "passive"))
    )
    (net (code "144") (name "unconnected-(R27-Pad2)") (class "Default")
      (node (ref "R27") (pin "2") (pinfunction "2_2") (pintype "passive"))
    )
    (net (code "145") (name "unconnected-(R28-Pad2)") (class "Default")
      (node (ref "R28") (pin "2") (pinfunction "2_2") (pintype "passive"))
    )
  )
)
